# photoboard2a.net
KiCad netlist of a schematic drawn in EAGLE
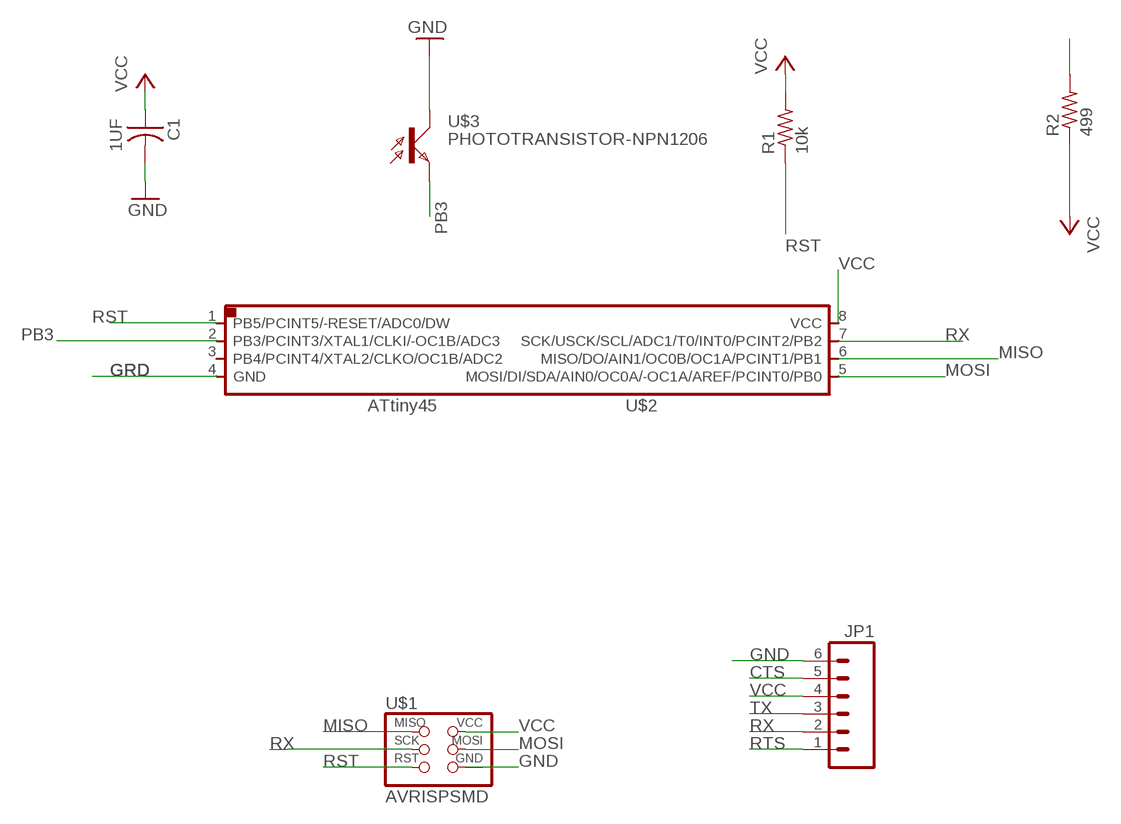
[diagram p0: schematic, sheet 1]

(export (version "E")
  (design (tool "Eeschema 10.0.6"))
  (components
    (comp (ref "C1")
      (value "1UF")
      (footprint "eagle-import:C1206FAB")
      (libsource (lib "eagle-import") (part "CAP-US1206FAB"))
    )
    (comp (ref "JP1")
      (value "M06SMD")
      (footprint "eagle-import:1X06-SMD")
      (libsource (lib "eagle-import") (part "M06SMD"))
    )
    (comp (ref "R1")
      (value "10k")
      (footprint "eagle-import:R1206")
      (libsource (lib "eagle-import") (part "RES-US1206"))
    )
    (comp (ref "R2")
      (value "499")
      (footprint "eagle-import:R1206")
      (libsource (lib "eagle-import") (part "RES-US1206"))
    )
    (comp (ref "U$1")
      (value "AVRISPSMD")
      (footprint "eagle-import:2X03SMD")
      (libsource (lib "eagle-import") (part "AVRISPSMD"))
    )
    (comp (ref "U$2")
      (value "ATTINY45SI")
      (footprint "eagle-import:SOIC8")
      (libsource (lib "eagle-import") (part "ATTINY45SI"))
    )
    (comp (ref "U$3")
      (value "PHOTOTRANSISTOR-NPN1206")
      (footprint "eagle-import:OP1206")
      (libsource (lib "eagle-import") (part "PHOTOTRANSISTOR-NPN1206"))
    )
  )
  (nets
    (net (code "1") (name "/CTS") (class "Default")
      (node (ref "JP1") (pin "5") (pinfunction "5_5") (pintype "passive"))
    )
    (net (code "2") (name "/GRD") (class "Default")
      (node (ref "U$2") (pin "4") (pinfunction "GND_4") (pintype "bidirectional"))
    )
    (net (code "3") (name "/MISO") (class "Default")
      (node (ref "U$1") (pin "1") (pinfunction "MISO_1") (pintype "passive"))
      (node (ref "U$2") (pin "6") (pinfunction "MISO/DO/AIN1/OC0B/OC1A/PCINT1/PB1_6") (pintype "bidirectional"))
    )
    (net (code "4") (name "/MOSI") (class "Default")
      (node (ref "U$1") (pin "4") (pinfunction "MOSI_4") (pintype "passive"))
      (node (ref "U$2") (pin "5") (pinfunction "MOSI/DI/SDA/AIN0/OC0A/-OC1A/AREF/PCINT0/PB0_5") (pintype "bidirectional"))
    )
    (net (code "5") (name "/PB3") (class "Default")
      (node (ref "R2") (pin "2") (pinfunction "2_2") (pintype "passive"))
      (node (ref "U$2") (pin "2") (pinfunction "PB3/PCINT3/XTAL1/CLKI/-OC1B/ADC3_2") (pintype "bidirectional"))
      (node (ref "U$3") (pin "EMITTER") (pinfunction "E_EMITTER") (pintype "passive"))
    )
    (net (code "6") (name "/RST") (class "Default")
      (node (ref "R1") (pin "1") (pinfunction "1_1") (pintype "passive"))
      (node (ref "U$1") (pin "5") (pinfunction "RST_5") (pintype "passive"))
      (node (ref "U$2") (pin "1") (pinfunction "PB5/PCINT5/-RESET/ADC0/DW_1") (pintype "bidirectional"))
    )
    (net (code "7") (name "/RTS") (class "Default")
      (node (ref "JP1") (pin "1") (pinfunction "1_1") (pintype "passive"))
    )
    (net (code "8") (name "/RX") (class "Default")
      (node (ref "JP1") (pin "2") (pinfunction "2_2") (pintype "passive"))
      (node (ref "U$1") (pin "3") (pinfunction "SCK_3") (pintype "passive"))
      (node (ref "U$2") (pin "7") (pinfunction "SCK/USCK/SCL/ADC1/T0/INT0/PCINT2/PB2_7") (pintype "bidirectional"))
    )
    (net (code "9") (name "/TX") (class "Default")
      (node (ref "JP1") (pin "3") (pinfunction "3_3") (pintype "passive"))
    )
    (net (code "10") (name "GND") (class "Default")
      (node (ref "C1") (pin "2") (pinfunction "2_2") (pintype "passive"))
      (node (ref "JP1") (pin "6") (pinfunction "6_6") (pintype "passive"))
      (node (ref "U$1") (pin "6") (pinfunction "GND_6") (pintype "passive"))
      (node (ref "U$3") (pin "COLLECTOR") (pinfunction "C_COLLECTOR") (pintype "passive"))
    )
    (net (code "11") (name "VCC") (class "Default")
      (node (ref "C1") (pin "1") (pinfunction "1_1") (pintype "passive"))
      (node (ref "JP1") (pin "4") (pinfunction "4_4") (pintype "passive"))
      (node (ref "R1") (pin "2") (pinfunction "2_2") (pintype "passive"))
      (node (ref "R2") (pin "1") (pinfunction "1_1") (pintype "passive"))
      (node (ref "U$1") (pin "2") (pinfunction "VCC_2") (pintype "passive"))
      (node (ref "U$2") (pin "8") (pinfunction "VCC_8") (pintype "bidirectional"))
    )
    (net (code "12") (name "unconnected-(U$2-PB4{slash}PCINT4{slash}XTAL2{slash}CLKO{slash}OC1B{slash}ADC2-Pad3)") (class "Default")
      (node (ref "U$2") (pin "3") (pinfunction "PB4/PCINT4/XTAL2/CLKO/OC1B/ADC2_3") (pintype "bidirectional"))
    )
  )
)
